# PatchPanel.net
KiCad netlist of a schematic drawn in EAGLE
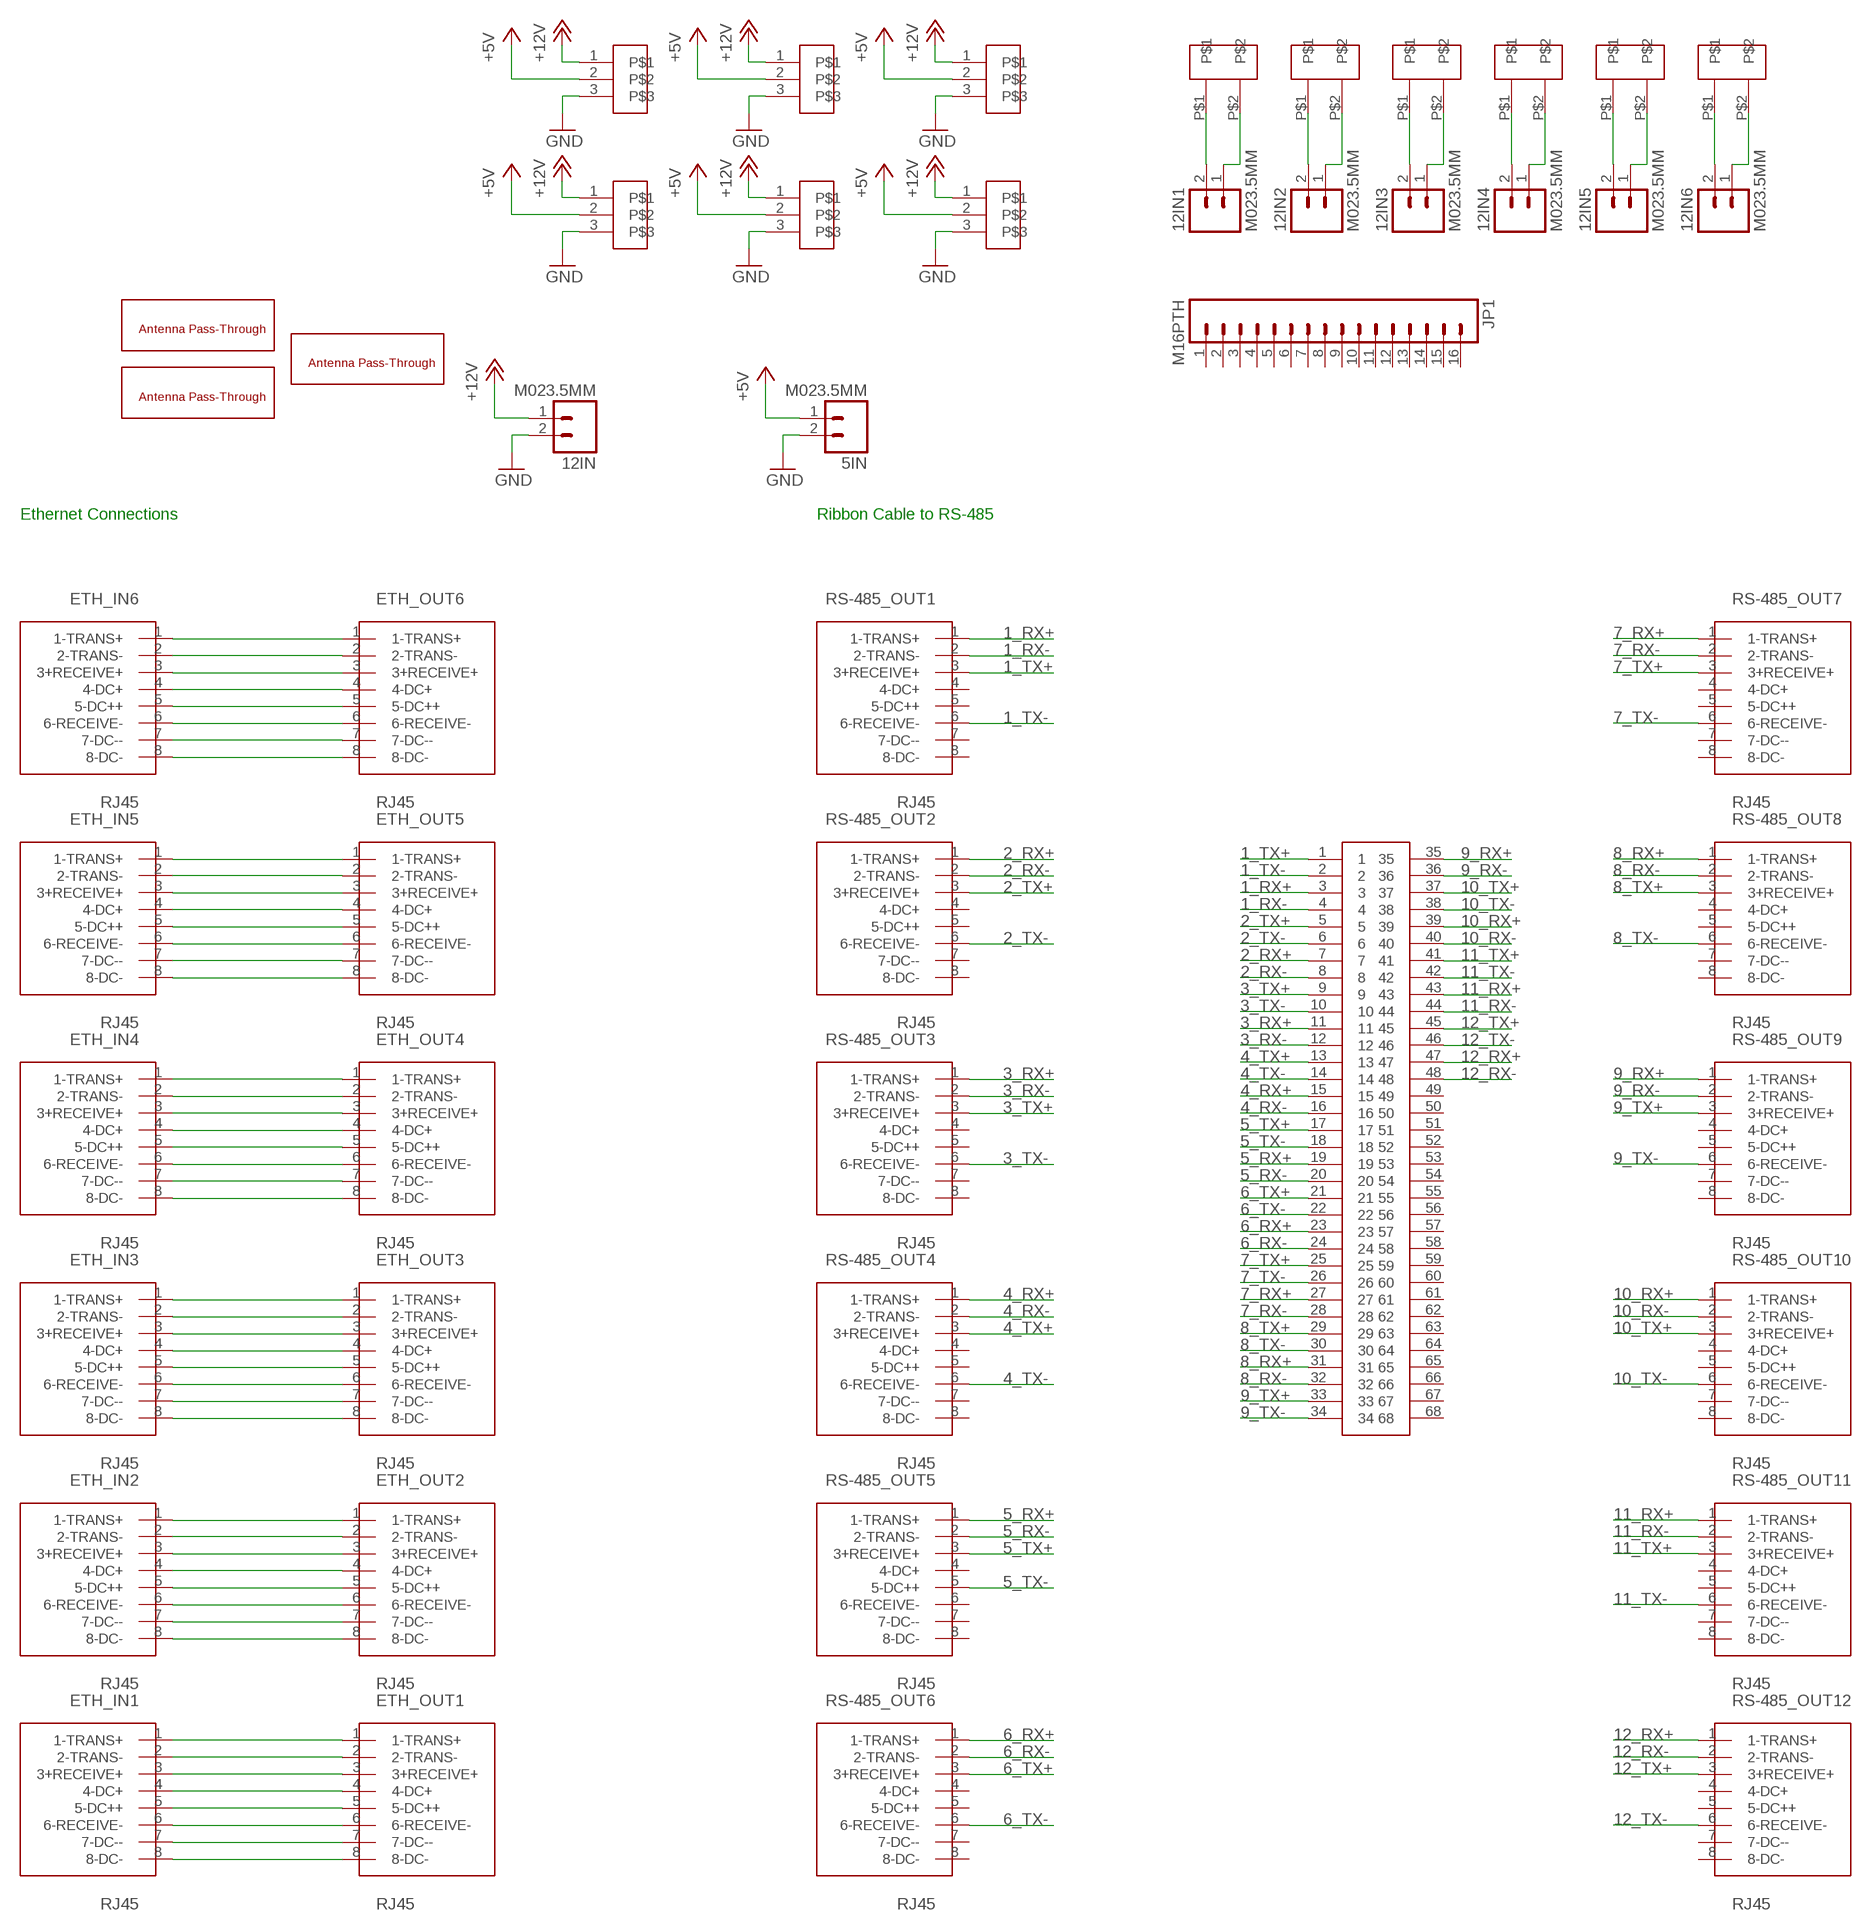
[diagram p0: schematic, sheet 1]

(export (version "E")
  (design (tool "Eeschema 10.0.6"))
  (components
    (comp (ref "5IN")
      (value "M023.5MM")
      (footprint "eagle-import:SCREWTERMINAL-3.5MM-2")
      (libsource (lib "eagle-import") (part "M023.5MM"))
    )
    (comp (ref "12IN")
      (value "M023.5MM")
      (footprint "eagle-import:SCREWTERMINAL-3.5MM-2")
      (libsource (lib "eagle-import") (part "M023.5MM"))
    )
    (comp (ref "12IN1")
      (value "M023.5MM")
      (footprint "eagle-import:SCREWTERMINAL-3.5MM-2")
      (libsource (lib "eagle-import") (part "M023.5MM"))
    )
    (comp (ref "12IN2")
      (value "M023.5MM")
      (footprint "eagle-import:SCREWTERMINAL-3.5MM-2")
      (libsource (lib "eagle-import") (part "M023.5MM"))
    )
    (comp (ref "12IN3")
      (value "M023.5MM")
      (footprint "eagle-import:SCREWTERMINAL-3.5MM-2")
      (libsource (lib "eagle-import") (part "M023.5MM"))
    )
    (comp (ref "12IN4")
      (value "M023.5MM")
      (footprint "eagle-import:SCREWTERMINAL-3.5MM-2")
      (libsource (lib "eagle-import") (part "M023.5MM"))
    )
    (comp (ref "12IN5")
      (value "M023.5MM")
      (footprint "eagle-import:SCREWTERMINAL-3.5MM-2")
      (libsource (lib "eagle-import") (part "M023.5MM"))
    )
    (comp (ref "12IN6")
      (value "M023.5MM")
      (footprint "eagle-import:SCREWTERMINAL-3.5MM-2")
      (libsource (lib "eagle-import") (part "M023.5MM"))
    )
    (comp (ref "ETH_IN1")
      (value "RJ45")
      (footprint "eagle-import:RJ45-CAT5E")
      (libsource (lib "eagle-import") (part "RJ45"))
    )
    (comp (ref "ETH_IN2")
      (value "RJ45")
      (footprint "eagle-import:RJ45-CAT5E")
      (libsource (lib "eagle-import") (part "RJ45"))
    )
    (comp (ref "ETH_IN3")
      (value "RJ45")
      (footprint "eagle-import:RJ45-CAT5E")
      (libsource (lib "eagle-import") (part "RJ45"))
    )
    (comp (ref "ETH_IN4")
      (value "RJ45")
      (footprint "eagle-import:RJ45-CAT5E")
      (libsource (lib "eagle-import") (part "RJ45"))
    )
    (comp (ref "ETH_IN5")
      (value "RJ45")
      (footprint "eagle-import:RJ45-CAT5E")
      (libsource (lib "eagle-import") (part "RJ45"))
    )
    (comp (ref "ETH_IN6")
      (value "RJ45")
      (footprint "eagle-import:RJ45-CAT5E")
      (libsource (lib "eagle-import") (part "RJ45"))
    )
    (comp (ref "ETH_OUT1")
      (value "RJ45")
      (footprint "eagle-import:RJ45-CAT5E")
      (libsource (lib "eagle-import") (part "RJ45"))
    )
    (comp (ref "ETH_OUT2")
      (value "RJ45")
      (footprint "eagle-import:RJ45-CAT5E")
      (libsource (lib "eagle-import") (part "RJ45"))
    )
    (comp (ref "ETH_OUT3")
      (value "RJ45")
      (footprint "eagle-import:RJ45-CAT5E")
      (libsource (lib "eagle-import") (part "RJ45"))
    )
    (comp (ref "ETH_OUT4")
      (value "RJ45")
      (footprint "eagle-import:RJ45-CAT5E")
      (libsource (lib "eagle-import") (part "RJ45"))
    )
    (comp (ref "ETH_OUT5")
      (value "RJ45")
      (footprint "eagle-import:RJ45-CAT5E")
      (libsource (lib "eagle-import") (part "RJ45"))
    )
    (comp (ref "ETH_OUT6")
      (value "RJ45")
      (footprint "eagle-import:RJ45-CAT5E")
      (libsource (lib "eagle-import") (part "RJ45"))
    )
    (comp (ref "JP1")
      (value "M16PTH")
      (footprint "eagle-import:1X16")
      (libsource (lib "eagle-import") (part "M16PTH"))
    )
    (comp (ref "RS-485_OUT1")
      (value "RJ45")
      (footprint "eagle-import:RJ45-CAT5E")
      (libsource (lib "eagle-import") (part "RJ45"))
    )
    (comp (ref "RS-485_OUT2")
      (value "RJ45")
      (footprint "eagle-import:RJ45-CAT5E")
      (libsource (lib "eagle-import") (part "RJ45"))
    )
    (comp (ref "RS-485_OUT3")
      (value "RJ45")
      (footprint "eagle-import:RJ45-CAT5E")
      (libsource (lib "eagle-import") (part "RJ45"))
    )
    (comp (ref "RS-485_OUT4")
      (value "RJ45")
      (footprint "eagle-import:RJ45-CAT5E")
      (libsource (lib "eagle-import") (part "RJ45"))
    )
    (comp (ref "RS-485_OUT5")
      (value "RJ45")
      (footprint "eagle-import:RJ45-CAT5E")
      (libsource (lib "eagle-import") (part "RJ45"))
    )
    (comp (ref "RS-485_OUT6")
      (value "RJ45")
      (footprint "eagle-import:RJ45-CAT5E")
      (libsource (lib "eagle-import") (part "RJ45"))
    )
    (comp (ref "RS-485_OUT7")
      (value "RJ45")
      (footprint "eagle-import:RJ45-CAT5E")
      (libsource (lib "eagle-import") (part "RJ45"))
    )
    (comp (ref "RS-485_OUT8")
      (value "RJ45")
      (footprint "eagle-import:RJ45-CAT5E")
      (libsource (lib "eagle-import") (part "RJ45"))
    )
    (comp (ref "RS-485_OUT9")
      (value "RJ45")
      (footprint "eagle-import:RJ45-CAT5E")
      (libsource (lib "eagle-import") (part "RJ45"))
    )
    (comp (ref "RS-485_OUT10")
      (value "RJ45")
      (footprint "eagle-import:RJ45-CAT5E")
      (libsource (lib "eagle-import") (part "RJ45"))
    )
    (comp (ref "RS-485_OUT11")
      (value "RJ45")
      (footprint "eagle-import:RJ45-CAT5E")
      (libsource (lib "eagle-import") (part "RJ45"))
    )
    (comp (ref "RS-485_OUT12")
      (value "RJ45")
      (footprint "eagle-import:RJ45-CAT5E")
      (libsource (lib "eagle-import") (part "RJ45"))
    )
    (comp (ref "U$1")
      (value "TB60050685100")
      (footprint "eagle-import:60050685100")
      (libsource (lib "eagle-import") (part "TB60050685100"))
    )
    (comp (ref "U$2")
      (value "3PIN")
      (footprint "eagle-import:0.93_")
      (libsource (lib "eagle-import") (part "3PIN"))
    )
    (comp (ref "U$3")
      (value "3PIN")
      (footprint "eagle-import:0.93_")
      (libsource (lib "eagle-import") (part "3PIN"))
    )
    (comp (ref "U$4")
      (value "3PIN")
      (footprint "eagle-import:0.93_")
      (libsource (lib "eagle-import") (part "3PIN"))
    )
    (comp (ref "U$5")
      (value "3PIN")
      (footprint "eagle-import:0.93_")
      (libsource (lib "eagle-import") (part "3PIN"))
    )
    (comp (ref "U$6")
      (value "3PIN")
      (footprint "eagle-import:0.93_")
      (libsource (lib "eagle-import") (part "3PIN"))
    )
    (comp (ref "U$7")
      (value "3PIN")
      (footprint "eagle-import:0.93_")
      (libsource (lib "eagle-import") (part "3PIN"))
    )
    (comp (ref "U$8")
      (value "MLX-2")
      (footprint "eagle-import:42002-2")
      (libsource (lib "eagle-import") (part "MLX-2"))
    )
    (comp (ref "U$9")
      (value "MLX-2")
      (footprint "eagle-import:42002-2")
      (libsource (lib "eagle-import") (part "MLX-2"))
    )
    (comp (ref "U$10")
      (value "MLX-2")
      (footprint "eagle-import:42002-2")
      (libsource (lib "eagle-import") (part "MLX-2"))
    )
    (comp (ref "U$11")
      (value "MLX-2")
      (footprint "eagle-import:42002-2")
      (libsource (lib "eagle-import") (part "MLX-2"))
    )
    (comp (ref "U$12")
      (value "MLX-2")
      (footprint "eagle-import:42002-2")
      (libsource (lib "eagle-import") (part "MLX-2"))
    )
    (comp (ref "U$13")
      (value "MLX-2")
      (footprint "eagle-import:42002-2")
      (libsource (lib "eagle-import") (part "MLX-2"))
    )
    (comp (ref "U$14")
      (value "N-TYPE-THRU")
      (footprint "eagle-import:N-TYPE")
      (libsource (lib "eagle-import") (part "N-TYPE-THRU"))
    )
    (comp (ref "U$15")
      (value "N-TYPE-THRU")
      (footprint "eagle-import:N-TYPE")
      (libsource (lib "eagle-import") (part "N-TYPE-THRU"))
    )
    (comp (ref "U$16")
      (value "SMA-THRU")
      (footprint "eagle-import:SMA")
      (libsource (lib "eagle-import") (part "SMA-THRU"))
    )
  )
  (nets
    (net (code "1") (name "+5V") (class "Default")
      (node (ref "5IN") (pin "1") (pinfunction "1_1") (pintype "passive"))
      (node (ref "U$2") (pin "2") (pinfunction "P$2_2") (pintype "bidirectional"))
      (node (ref "U$3") (pin "2") (pinfunction "P$2_2") (pintype "bidirectional"))
      (node (ref "U$4") (pin "2") (pinfunction "P$2_2") (pintype "bidirectional"))
      (node (ref "U$5") (pin "2") (pinfunction "P$2_2") (pintype "bidirectional"))
      (node (ref "U$6") (pin "2") (pinfunction "P$2_2") (pintype "bidirectional"))
      (node (ref "U$7") (pin "2") (pinfunction "P$2_2") (pintype "bidirectional"))
    )
    (net (code "2") (name "+12V") (class "Default")
      (node (ref "12IN") (pin "1") (pinfunction "1_1") (pintype "passive"))
      (node (ref "U$2") (pin "1") (pinfunction "P$1_1") (pintype "bidirectional"))
      (node (ref "U$3") (pin "1") (pinfunction "P$1_1") (pintype "bidirectional"))
      (node (ref "U$4") (pin "1") (pinfunction "P$1_1") (pintype "bidirectional"))
      (node (ref "U$5") (pin "1") (pinfunction "P$1_1") (pintype "bidirectional"))
      (node (ref "U$6") (pin "1") (pinfunction "P$1_1") (pintype "bidirectional"))
      (node (ref "U$7") (pin "1") (pinfunction "P$1_1") (pintype "bidirectional"))
    )
    (net (code "3") (name "/1_RX+") (class "Default")
      (node (ref "RS-485_OUT1") (pin "1") (pinfunction "1-TRANS+_1") (pintype "bidirectional"))
      (node (ref "U$1") (pin "3") (pinfunction "3_3") (pintype "bidirectional"))
    )
    (net (code "4") (name "/1_RX-") (class "Default")
      (node (ref "RS-485_OUT1") (pin "2") (pinfunction "2-TRANS-_2") (pintype "bidirectional"))
      (node (ref "U$1") (pin "4") (pinfunction "4_4") (pintype "bidirectional"))
    )
    (net (code "5") (name "/1_TX+") (class "Default")
      (node (ref "RS-485_OUT1") (pin "3") (pinfunction "3+RECEIVE+_3") (pintype "bidirectional"))
      (node (ref "U$1") (pin "1") (pinfunction "1_1") (pintype "bidirectional"))
    )
    (net (code "6") (name "/1_TX-") (class "Default")
      (node (ref "RS-485_OUT1") (pin "6") (pinfunction "6-RECEIVE-_6") (pintype "bidirectional"))
      (node (ref "U$1") (pin "2") (pinfunction "2_2") (pintype "bidirectional"))
    )
    (net (code "7") (name "/2_RX+") (class "Default")
      (node (ref "RS-485_OUT2") (pin "1") (pinfunction "1-TRANS+_1") (pintype "bidirectional"))
      (node (ref "U$1") (pin "7") (pinfunction "7_7") (pintype "bidirectional"))
    )
    (net (code "8") (name "/2_RX-") (class "Default")
      (node (ref "RS-485_OUT2") (pin "2") (pinfunction "2-TRANS-_2") (pintype "bidirectional"))
      (node (ref "U$1") (pin "8") (pinfunction "8_8") (pintype "bidirectional"))
    )
    (net (code "9") (name "/2_TX+") (class "Default")
      (node (ref "RS-485_OUT2") (pin "3") (pinfunction "3+RECEIVE+_3") (pintype "bidirectional"))
      (node (ref "U$1") (pin "5") (pinfunction "5_5") (pintype "bidirectional"))
    )
    (net (code "10") (name "/2_TX-") (class "Default")
      (node (ref "RS-485_OUT2") (pin "6") (pinfunction "6-RECEIVE-_6") (pintype "bidirectional"))
      (node (ref "U$1") (pin "6") (pinfunction "6_6") (pintype "bidirectional"))
    )
    (net (code "11") (name "/3_RX+") (class "Default")
      (node (ref "RS-485_OUT3") (pin "1") (pinfunction "1-TRANS+_1") (pintype "bidirectional"))
      (node (ref "U$1") (pin "11") (pinfunction "11_11") (pintype "bidirectional"))
    )
    (net (code "12") (name "/3_RX-") (class "Default")
      (node (ref "RS-485_OUT3") (pin "2") (pinfunction "2-TRANS-_2") (pintype "bidirectional"))
      (node (ref "U$1") (pin "12") (pinfunction "12_12") (pintype "bidirectional"))
    )
    (net (code "13") (name "/3_TX+") (class "Default")
      (node (ref "RS-485_OUT3") (pin "3") (pinfunction "3+RECEIVE+_3") (pintype "bidirectional"))
      (node (ref "U$1") (pin "9") (pinfunction "9_9") (pintype "bidirectional"))
    )
    (net (code "14") (name "/3_TX-") (class "Default")
      (node (ref "RS-485_OUT3") (pin "6") (pinfunction "6-RECEIVE-_6") (pintype "bidirectional"))
      (node (ref "U$1") (pin "10") (pinfunction "10_10") (pintype "bidirectional"))
    )
    (net (code "15") (name "/4_RX+") (class "Default")
      (node (ref "RS-485_OUT4") (pin "1") (pinfunction "1-TRANS+_1") (pintype "bidirectional"))
      (node (ref "U$1") (pin "15") (pinfunction "15_15") (pintype "bidirectional"))
    )
    (net (code "16") (name "/4_RX-") (class "Default")
      (node (ref "RS-485_OUT4") (pin "2") (pinfunction "2-TRANS-_2") (pintype "bidirectional"))
      (node (ref "U$1") (pin "16") (pinfunction "16_16") (pintype "bidirectional"))
    )
    (net (code "17") (name "/4_TX+") (class "Default")
      (node (ref "RS-485_OUT4") (pin "3") (pinfunction "3+RECEIVE+_3") (pintype "bidirectional"))
      (node (ref "U$1") (pin "13") (pinfunction "13_13") (pintype "bidirectional"))
    )
    (net (code "18") (name "/4_TX-") (class "Default")
      (node (ref "RS-485_OUT4") (pin "6") (pinfunction "6-RECEIVE-_6") (pintype "bidirectional"))
      (node (ref "U$1") (pin "14") (pinfunction "14_14") (pintype "bidirectional"))
    )
    (net (code "19") (name "/5_RX+") (class "Default")
      (node (ref "RS-485_OUT5") (pin "1") (pinfunction "1-TRANS+_1") (pintype "bidirectional"))
      (node (ref "U$1") (pin "19") (pinfunction "19_19") (pintype "bidirectional"))
    )
    (net (code "20") (name "/5_RX-") (class "Default")
      (node (ref "RS-485_OUT5") (pin "2") (pinfunction "2-TRANS-_2") (pintype "bidirectional"))
      (node (ref "U$1") (pin "20") (pinfunction "20_20") (pintype "bidirectional"))
    )
    (net (code "21") (name "/5_TX+") (class "Default")
      (node (ref "RS-485_OUT5") (pin "3") (pinfunction "3+RECEIVE+_3") (pintype "bidirectional"))
      (node (ref "U$1") (pin "17") (pinfunction "17_17") (pintype "bidirectional"))
    )
    (net (code "22") (name "/5_TX-") (class "Default")
      (node (ref "RS-485_OUT5") (pin "5") (pinfunction "5-DC++_5") (pintype "bidirectional"))
      (node (ref "U$1") (pin "18") (pinfunction "18_18") (pintype "bidirectional"))
    )
    (net (code "23") (name "/6_RX+") (class "Default")
      (node (ref "RS-485_OUT6") (pin "1") (pinfunction "1-TRANS+_1") (pintype "bidirectional"))
      (node (ref "U$1") (pin "23") (pinfunction "23_23") (pintype "bidirectional"))
    )
    (net (code "24") (name "/6_RX-") (class "Default")
      (node (ref "RS-485_OUT6") (pin "2") (pinfunction "2-TRANS-_2") (pintype "bidirectional"))
      (node (ref "U$1") (pin "24") (pinfunction "24_24") (pintype "bidirectional"))
    )
    (net (code "25") (name "/6_TX+") (class "Default")
      (node (ref "RS-485_OUT6") (pin "3") (pinfunction "3+RECEIVE+_3") (pintype "bidirectional"))
      (node (ref "U$1") (pin "21") (pinfunction "21_21") (pintype "bidirectional"))
    )
    (net (code "26") (name "/6_TX-") (class "Default")
      (node (ref "RS-485_OUT6") (pin "6") (pinfunction "6-RECEIVE-_6") (pintype "bidirectional"))
      (node (ref "U$1") (pin "22") (pinfunction "22_22") (pintype "bidirectional"))
    )
    (net (code "27") (name "/7_RX+") (class "Default")
      (node (ref "RS-485_OUT7") (pin "1") (pinfunction "1-TRANS+_1") (pintype "bidirectional"))
      (node (ref "U$1") (pin "27") (pinfunction "27_27") (pintype "bidirectional"))
    )
    (net (code "28") (name "/7_RX-") (class "Default")
      (node (ref "RS-485_OUT7") (pin "2") (pinfunction "2-TRANS-_2") (pintype "bidirectional"))
      (node (ref "U$1") (pin "28") (pinfunction "28_28") (pintype "bidirectional"))
    )
    (net (code "29") (name "/7_TX+") (class "Default")
      (node (ref "RS-485_OUT7") (pin "3") (pinfunction "3+RECEIVE+_3") (pintype "bidirectional"))
      (node (ref "U$1") (pin "25") (pinfunction "25_25") (pintype "bidirectional"))
    )
    (net (code "30") (name "/7_TX-") (class "Default")
      (node (ref "RS-485_OUT7") (pin "6") (pinfunction "6-RECEIVE-_6") (pintype "bidirectional"))
      (node (ref "U$1") (pin "26") (pinfunction "26_26") (pintype "bidirectional"))
    )
    (net (code "31") (name "/8_RX+") (class "Default")
      (node (ref "RS-485_OUT8") (pin "1") (pinfunction "1-TRANS+_1") (pintype "bidirectional"))
      (node (ref "U$1") (pin "31") (pinfunction "31_31") (pintype "bidirectional"))
    )
    (net (code "32") (name "/8_RX-") (class "Default")
      (node (ref "RS-485_OUT8") (pin "2") (pinfunction "2-TRANS-_2") (pintype "bidirectional"))
      (node (ref "U$1") (pin "32") (pinfunction "32_32") (pintype "bidirectional"))
    )
    (net (code "33") (name "/8_TX+") (class "Default")
      (node (ref "RS-485_OUT8") (pin "3") (pinfunction "3+RECEIVE+_3") (pintype "bidirectional"))
      (node (ref "U$1") (pin "29") (pinfunction "29_29") (pintype "bidirectional"))
    )
    (net (code "34") (name "/8_TX-") (class "Default")
      (node (ref "RS-485_OUT8") (pin "6") (pinfunction "6-RECEIVE-_6") (pintype "bidirectional"))
      (node (ref "U$1") (pin "30") (pinfunction "30_30") (pintype "bidirectional"))
    )
    (net (code "35") (name "/9_RX+") (class "Default")
      (node (ref "RS-485_OUT9") (pin "1") (pinfunction "1-TRANS+_1") (pintype "bidirectional"))
      (node (ref "U$1") (pin "35") (pinfunction "35_35") (pintype "bidirectional"))
    )
    (net (code "36") (name "/9_RX-") (class "Default")
      (node (ref "RS-485_OUT9") (pin "2") (pinfunction "2-TRANS-_2") (pintype "bidirectional"))
      (node (ref "U$1") (pin "36") (pinfunction "36_36") (pintype "bidirectional"))
    )
    (net (code "37") (name "/9_TX+") (class "Default")
      (node (ref "RS-485_OUT9") (pin "3") (pinfunction "3+RECEIVE+_3") (pintype "bidirectional"))
      (node (ref "U$1") (pin "33") (pinfunction "33_33") (pintype "bidirectional"))
    )
    (net (code "38") (name "/9_TX-") (class "Default")
      (node (ref "RS-485_OUT9") (pin "6") (pinfunction "6-RECEIVE-_6") (pintype "bidirectional"))
      (node (ref "U$1") (pin "34") (pinfunction "34_34") (pintype "bidirectional"))
    )
    (net (code "39") (name "/10_RX+") (class "Default")
      (node (ref "RS-485_OUT10") (pin "1") (pinfunction "1-TRANS+_1") (pintype "bidirectional"))
      (node (ref "U$1") (pin "39") (pinfunction "39_39") (pintype "bidirectional"))
    )
    (net (code "40") (name "/10_RX-") (class "Default")
      (node (ref "RS-485_OUT10") (pin "2") (pinfunction "2-TRANS-_2") (pintype "bidirectional"))
      (node (ref "U$1") (pin "40") (pinfunction "40_40") (pintype "bidirectional"))
    )
    (net (code "41") (name "/10_TX+") (class "Default")
      (node (ref "RS-485_OUT10") (pin "3") (pinfunction "3+RECEIVE+_3") (pintype "bidirectional"))
      (node (ref "U$1") (pin "37") (pinfunction "37_37") (pintype "bidirectional"))
    )
    (net (code "42") (name "/10_TX-") (class "Default")
      (node (ref "RS-485_OUT10") (pin "6") (pinfunction "6-RECEIVE-_6") (pintype "bidirectional"))
      (node (ref "U$1") (pin "38") (pinfunction "38_38") (pintype "bidirectional"))
    )
    (net (code "43") (name "/11_RX+") (class "Default")
      (node (ref "RS-485_OUT11") (pin "1") (pinfunction "1-TRANS+_1") (pintype "bidirectional"))
      (node (ref "U$1") (pin "43") (pinfunction "43_43") (pintype "bidirectional"))
    )
    (net (code "44") (name "/11_RX-") (class "Default")
      (node (ref "RS-485_OUT11") (pin "2") (pinfunction "2-TRANS-_2") (pintype "bidirectional"))
      (node (ref "U$1") (pin "44") (pinfunction "44_44") (pintype "bidirectional"))
    )
    (net (code "45") (name "/11_TX+") (class "Default")
      (node (ref "RS-485_OUT11") (pin "3") (pinfunction "3+RECEIVE+_3") (pintype "bidirectional"))
      (node (ref "U$1") (pin "41") (pinfunction "41_41") (pintype "bidirectional"))
    )
    (net (code "46") (name "/11_TX-") (class "Default")
      (node (ref "RS-485_OUT11") (pin "6") (pinfunction "6-RECEIVE-_6") (pintype "bidirectional"))
      (node (ref "U$1") (pin "42") (pinfunction "42_42") (pintype "bidirectional"))
    )
    (net (code "47") (name "/12_RX+") (class "Default")
      (node (ref "RS-485_OUT12") (pin "1") (pinfunction "1-TRANS+_1") (pintype "bidirectional"))
      (node (ref "U$1") (pin "47") (pinfunction "47_47") (pintype "bidirectional"))
    )
    (net (code "48") (name "/12_RX-") (class "Default")
      (node (ref "RS-485_OUT12") (pin "2") (pinfunction "2-TRANS-_2") (pintype "bidirectional"))
      (node (ref "U$1") (pin "48") (pinfunction "48_48") (pintype "bidirectional"))
    )
    (net (code "49") (name "/12_TX+") (class "Default")
      (node (ref "RS-485_OUT12") (pin "3") (pinfunction "3+RECEIVE+_3") (pintype "bidirectional"))
      (node (ref "U$1") (pin "45") (pinfunction "45_45") (pintype "bidirectional"))
    )
    (net (code "50") (name "/12_TX-") (class "Default")
      (node (ref "RS-485_OUT12") (pin "6") (pinfunction "6-RECEIVE-_6") (pintype "bidirectional"))
      (node (ref "U$1") (pin "46") (pinfunction "46_46") (pintype "bidirectional"))
    )
    (net (code "51") (name "GND") (class "Default")
      (node (ref "12IN") (pin "2") (pinfunction "2_2") (pintype "passive"))
      (node (ref "5IN") (pin "2") (pinfunction "2_2") (pintype "passive"))
      (node (ref "U$2") (pin "3") (pinfunction "P$3_3") (pintype "bidirectional"))
      (node (ref "U$3") (pin "3") (pinfunction "P$3_3") (pintype "bidirectional"))
      (node (ref "U$4") (pin "3") (pinfunction "P$3_3") (pintype "bidirectional"))
      (node (ref "U$5") (pin "3") (pinfunction "P$3_3") (pintype "bidirectional"))
      (node (ref "U$6") (pin "3") (pinfunction "P$3_3") (pintype "bidirectional"))
      (node (ref "U$7") (pin "3") (pinfunction "P$3_3") (pintype "bidirectional"))
    )
    (net (code "52") (name "Net-(12IN1-Pad1)") (class "Default")
      (node (ref "12IN1") (pin "1") (pinfunction "1_1") (pintype "passive"))
      (node (ref "U$8") (pin "P$2") (pinfunction "P$2_P$2") (pintype "bidirectional"))
    )
    (net (code "53") (name "Net-(12IN1-Pad2)") (class "Default")
      (node (ref "12IN1") (pin "2") (pinfunction "2_2") (pintype "passive"))
      (node (ref "U$8") (pin "P$1") (pinfunction "P$1_P$1") (pintype "bidirectional"))
    )
    (net (code "54") (name "Net-(12IN2-Pad1)") (class "Default")
      (node (ref "12IN2") (pin "1") (pinfunction "1_1") (pintype "passive"))
      (node (ref "U$9") (pin "P$2") (pinfunction "P$2_P$2") (pintype "bidirectional"))
    )
    (net (code "55") (name "Net-(12IN2-Pad2)") (class "Default")
      (node (ref "12IN2") (pin "2") (pinfunction "2_2") (pintype "passive"))
      (node (ref "U$9") (pin "P$1") (pinfunction "P$1_P$1") (pintype "bidirectional"))
    )
    (net (code "56") (name "Net-(12IN3-Pad1)") (class "Default")
      (node (ref "12IN3") (pin "1") (pinfunction "1_1") (pintype "passive"))
      (node (ref "U$10") (pin "P$2") (pinfunction "P$2_P$2") (pintype "bidirectional"))
    )
    (net (code "57") (name "Net-(12IN3-Pad2)") (class "Default")
      (node (ref "12IN3") (pin "2") (pinfunction "2_2") (pintype "passive"))
      (node (ref "U$10") (pin "P$1") (pinfunction "P$1_P$1") (pintype "bidirectional"))
    )
    (net (code "58") (name "Net-(12IN4-Pad1)") (class "Default")
      (node (ref "12IN4") (pin "1") (pinfunction "1_1") (pintype "passive"))
      (node (ref "U$11") (pin "P$2") (pinfunction "P$2_P$2") (pintype "bidirectional"))
    )
    (net (code "59") (name "Net-(12IN4-Pad2)") (class "Default")
      (node (ref "12IN4") (pin "2") (pinfunction "2_2") (pintype "passive"))
      (node (ref "U$11") (pin "P$1") (pinfunction "P$1_P$1") (pintype "bidirectional"))
    )
    (net (code "60") (name "Net-(12IN5-Pad1)") (class "Default")
      (node (ref "12IN5") (pin "1") (pinfunction "1_1") (pintype "passive"))
      (node (ref "U$12") (pin "P$2") (pinfunction "P$2_P$2") (pintype "bidirectional"))
    )
    (net (code "61") (name "Net-(12IN5-Pad2)") (class "Default")
      (node (ref "12IN5") (pin "2") (pinfunction "2_2") (pintype "passive"))
      (node (ref "U$12") (pin "P$1") (pinfunction "P$1_P$1") (pintype "bidirectional"))
    )
    (net (code "62") (name "Net-(12IN6-Pad1)") (class "Default")
      (node (ref "12IN6") (pin "1") (pinfunction "1_1") (pintype "passive"))
      (node (ref "U$13") (pin "P$2") (pinfunction "P$2_P$2") (pintype "bidirectional"))
    )
    (net (code "63") (name "Net-(12IN6-Pad2)") (class "Default")
      (node (ref "12IN6") (pin "2") (pinfunction "2_2") (pintype "passive"))
      (node (ref "U$13") (pin "P$1") (pinfunction "P$1_P$1") (pintype "bidirectional"))
    )
    (net (code "64") (name "Net-(ETH_IN1-1-TRANS+)") (class "Default")
      (node (ref "ETH_IN1") (pin "1") (pinfunction "1-TRANS+_1") (pintype "bidirectional"))
      (node (ref "ETH_OUT1") (pin "1") (pinfunction "1-TRANS+_1") (pintype "bidirectional"))
    )
    (net (code "65") (name "Net-(ETH_IN1-2-TRANS-)") (class "Default")
      (node (ref "ETH_IN1") (pin "2") (pinfunction "2-TRANS-_2") (pintype "bidirectional"))
      (node (ref "ETH_OUT1") (pin "2") (pinfunction "2-TRANS-_2") (pintype "bidirectional"))
    )
    (net (code "66") (name "Net-(ETH_IN1-3+RECEIVE+)") (class "Default")
      (node (ref "ETH_IN1") (pin "3") (pinfunction "3+RECEIVE+_3") (pintype "bidirectional"))
      (node (ref "ETH_OUT1") (pin "3") (pinfunction "3+RECEIVE+_3") (pintype "bidirectional"))
    )
    (net (code "67") (name "Net-(ETH_IN1-4-DC+)") (class "Default")
      (node (ref "ETH_IN1") (pin "4") (pinfunction "4-DC+_4") (pintype "bidirectional"))
      (node (ref "ETH_OUT1") (pin "4") (pinfunction "4-DC+_4") (pintype "bidirectional"))
    )
    (net (code "68") (name "Net-(ETH_IN1-5-DC++)") (class "Default")
      (node (ref "ETH_IN1") (pin "5") (pinfunction "5-DC++_5") (pintype "bidirectional"))
      (node (ref "ETH_OUT1") (pin "5") (pinfunction "5-DC++_5") (pintype "bidirectional"))
    )
    (net (code "69") (name "Net-(ETH_IN1-6-RECEIVE-)") (class "Default")
      (node (ref "ETH_IN1") (pin "6") (pinfunction "6-RECEIVE-_6") (pintype "bidirectional"))
      (node (ref "ETH_OUT1") (pin "6") (pinfunction "6-RECEIVE-_6") (pintype "bidirectional"))
    )
    (net (code "70") (name "Net-(ETH_IN1-7-DC--)") (class "Default")
      (node (ref "ETH_IN1") (pin "7") (pinfunction "7-DC--_7") (pintype "bidirectional"))
      (node (ref "ETH_OUT1") (pin "7") (pinfunction "7-DC--_7") (pintype "bidirectional"))
    )
    (net (code "71") (name "Net-(ETH_IN1-8-DC-)") (class "Default")
      (node (ref "ETH_IN1") (pin "8") (pinfunction "8-DC-_8") (pintype "bidirectional"))
      (node (ref "ETH_OUT1") (pin "8") (pinfunction "8-DC-_8") (pintype "bidirectional"))
    )
    (net (code "72") (name "Net-(ETH_IN2-1-TRANS+)") (class "Default")
      (node (ref "ETH_IN2") (pin "1") (pinfunction "1-TRANS+_1") (pintype "bidirectional"))
      (node (ref "ETH_OUT2") (pin "1") (pinfunction "1-TRANS+_1") (pintype "bidirectional"))
    )
    (net (code "73") (name "Net-(ETH_IN2-2-TRANS-)") (class "Default")
      (node (ref "ETH_IN2") (pin "2") (pinfunction "2-TRANS-_2") (pintype "bidirectional"))
      (node (ref "ETH_OUT2") (pin "2") (pinfunction "2-TRANS-_2") (pintype "bidirectional"))
    )
    (net (code "74") (name "Net-(ETH_IN2-3+RECEIVE+)") (class "Default")
      (node (ref "ETH_IN2") (pin "3") (pinfunction "3+RECEIVE+_3") (pintype "bidirectional"))
      (node (ref "ETH_OUT2") (pin "3") (pinfunction "3+RECEIVE+_3") (pintype "bidirectional"))
    )
    (net (code "75") (name "Net-(ETH_IN2-4-DC+)") (class "Default")
      (node (ref "ETH_IN2") (pin "4") (pinfunction "4-DC+_4") (pintype "bidirectional"))
      (node (ref "ETH_OUT2") (pin "4") (pinfunction "4-DC+_4") (pintype "bidirectional"))
    )
    (net (code "76") (name "Net-(ETH_IN2-5-DC++)") (class "Default")
      (node (ref "ETH_IN2") (pin "5") (pinfunction "5-DC++_5") (pintype "bidirectional"))
      (node (ref "ETH_OUT2") (pin "5") (pinfunction "5-DC++_5") (pintype "bidirectional"))
    )
    (net (code "77") (name "Net-(ETH_IN2-6-RECEIVE-)") (class "Default")
      (node (ref "ETH_IN2") (pin "6") (pinfunction "6-RECEIVE-_6") (pintype "bidirectional"))
      (node (ref "ETH_OUT2") (pin "6") (pinfunction "6-RECEIVE-_6") (pintype "bidirectional"))
    )
    (net (code "78") (name "Net-(ETH_IN2-7-DC--)") (class "Default")
      (node (ref "ETH_IN2") (pin "7") (pinfunction "7-DC--_7") (pintype "bidirectional"))
      (node (ref "ETH_OUT2") (pin "7") (pinfunction "7-DC--_7") (pintype "bidirectional"))
    )
    (net (code "79") (name "Net-(ETH_IN2-8-DC-)") (class "Default")
      (node (ref "ETH_IN2") (pin "8") (pinfunction "8-DC-_8") (pintype "bidirectional"))
      (node (ref "ETH_OUT2") (pin "8") (pinfunction "8-DC-_8") (pintype "bidirectional"))
    )
    (net (code "80") (name "Net-(ETH_IN3-1-TRANS+)") (class "Default")
      (node (ref "ETH_IN3") (pin "1") (pinfunction "1-TRANS+_1") (pintype "bidirectional"))
      (node (ref "ETH_OUT3") (pin "1") (pinfunction "1-TRANS+_1") (pintype "bidirectional"))
    )
    (net (code "81") (name "Net-(ETH_IN3-2-TRANS-)") (class "Default")
      (node (ref "ETH_IN3") (pin "2") (pinfunction "2-TRANS-_2") (pintype "bidirectional"))
      (node (ref "ETH_OUT3") (pin "2") (pinfunction "2-TRANS-_2") (pintype "bidirectional"))
    )
    (net (code "82") (name "Net-(ETH_IN3-3+RECEIVE+)") (class "Default")
      (node (ref "ETH_IN3") (pin "3") (pinfunction "3+RECEIVE+_3") (pintype "bidirectional"))
      (node (ref "ETH_OUT3") (pin "3") (pinfunction "3+RECEIVE+_3") (pintype "bidirectional"))
    )
    (net (code "83") (name "Net-(ETH_IN3-4-DC+)") (class "Default")
      (node (ref "ETH_IN3") (pin "4") (pinfunction "4-DC+_4") (pintype "bidirectional"))
      (node (ref "ETH_OUT3") (pin "4") (pinfunction "4-DC+_4") (pintype "bidirectional"))
    )
    (net (code "84") (name "Net-(ETH_IN3-5-DC++)") (class "Default")
      (node (ref "ETH_IN3") (pin "5") (pinfunction "5-DC++_5") (pintype "bidirectional"))
      (node (ref "ETH_OUT3") (pin "5") (pinfunction "5-DC++_5") (pintype "bidirectional"))
    )
    (net (code "85") (name "Net-(ETH_IN3-6-RECEIVE-)") (class "Default")
      (node (ref "ETH_IN3") (pin "6") (pinfunction "6-RECEIVE-_6") (pintype "bidirectional"))
      (node (ref "ETH_OUT3") (pin "6") (pinfunction "6-RECEIVE-_6") (pintype "bidirectional"))
    )
    (net (code "86") (name "Net-(ETH_IN3-7-DC--)") (class "Default")
      (node (ref "ETH_IN3") (pin "7") (pinfunction "7-DC--_7") (pintype "bidirectional"))
      (node (ref "ETH_OUT3") (pin "7") (pinfunction "7-DC--_7") (pintype "bidirectional"))
    )
    (net (code "87") (name "Net-(ETH_IN3-8-DC-)") (class "Default")
      (node (ref "ETH_IN3") (pin "8") (pinfunction "8-DC-_8") (pintype "bidirectional"))
      (node (ref "ETH_OUT3") (pin "8") (pinfunction "8-DC-_8") (pintype "bidirectional"))
    )
    (net (code "88") (name "Net-(ETH_IN4-1-TRANS+)") (class "Default")
      (node (ref "ETH_IN4") (pin "1") (pinfunction "1-TRANS+_1") (pintype "bidirectional"))
      (node (ref "ETH_OUT4") (pin "1") (pinfunction "1-TRANS+_1") (pintype "bidirectional"))
    )
    (net (code "89") (name "Net-(ETH_IN4-2-TRANS-)") (class "Default")
      (node (ref "ETH_IN4") (pin "2") (pinfunction "2-TRANS-_2") (pintype "bidirectional"))
      (node (ref "ETH_OUT4") (pin "2") (pinfunction "2-TRANS-_2") (pintype "bidirectional"))
    )
    (net (code "90") (name "Net-(ETH_IN4-3+RECEIVE+)") (class "Default")
      (node (ref "ETH_IN4") (pin "3") (pinfunction "3+RECEIVE+_3") (pintype "bidirectional"))
      (node (ref "ETH_OUT4") (pin "3") (pinfunction "3+RECEIVE+_3") (pintype "bidirectional"))
    )
    (net (code "91") (name "Net-(ETH_IN4-4-DC+)") (class "Default")
      (node (ref "ETH_IN4") (pin "4") (pinfunction "4-DC+_4") (pintype "bidirectional"))
      (node (ref "ETH_OUT4") (pin "4") (pinfunction "4-DC+_4") (pintype "bidirectional"))
    )
    (net (code "92") (name "Net-(ETH_IN4-5-DC++)") (class "Default")
      (node (ref "ETH_IN4") (pin "5") (pinfunction "5-DC++_5") (pintype "bidirectional"))
      (node (ref "ETH_OUT4") (pin "5") (pinfunction "5-DC++_5") (pintype "bidirectional"))
    )
    (net (code "93") (name "Net-(ETH_IN4-6-RECEIVE-)") (class "Default")
      (node (ref "ETH_IN4") (pin "6") (pinfunction "6-RECEIVE-_6") (pintype "bidirectional"))
      (node (ref "ETH_OUT4") (pin "6") (pinfunction "6-RECEIVE-_6") (pintype "bidirectional"))
    )
    (net (code "94") (name "Net-(ETH_IN4-7-DC--)") (class "Default")
      (node (ref "ETH_IN4") (pin "7") (pinfunction "7-DC--_7") (pintype "bidirectional"))
      (node (ref "ETH_OUT4") (pin "7") (pinfunction "7-DC--_7") (pintype "bidirectional"))
    )
    (net (code "95") (name "Net-(ETH_IN4-8-DC-)") (class "Default")
      (node (ref "ETH_IN4") (pin "8") (pinfunction "8-DC-_8") (pintype "bidirectional"))
      (node (ref "ETH_OUT4") (pin "8") (pinfunction "8-DC-_8") (pintype "bidirectional"))
    )
    (net (code "96") (name "Net-(ETH_IN5-1-TRANS+)") (class "Default")
      (node (ref "ETH_IN5") (pin "1") (pinfunction "1-TRANS+_1") (pintype "bidirectional"))
      (node (ref "ETH_OUT5") (pin "1") (pinfunction "1-TRANS+_1") (pintype "bidirectional"))
    )
    (net (code "97") (name "Net-(ETH_IN5-2-TRANS-)") (class "Default")
      (node (ref "ETH_IN5") (pin "2") (pinfunction "2-TRANS-_2") (pintype "bidirectional"))
      (node (ref "ETH_OUT5") (pin "2") (pinfunction "2-TRANS-_2") (pintype "bidirectional"))
    )
    (net (code "98") (name "Net-(ETH_IN5-3+RECEIVE+)") (class "Default")
      (node (ref "ETH_IN5") (pin "3") (pinfunction "3+RECEIVE+_3") (pintype "bidirectional"))
      (node (ref "ETH_OUT5") (pin "3") (pinfunction "3+RECEIVE+_3") (pintype "bidirectional"))
    )
    (net (code "99") (name "Net-(ETH_IN5-4-DC+)") (class "Default")
      (node (ref "ETH_IN5") (pin "4") (pinfunction "4-DC+_4") (pintype "bidirectional"))
      (node (ref "ETH_OUT5") (pin "4") (pinfunction "4-DC+_4") (pintype "bidirectional"))
    )
    (net (code "100") (name "Net-(ETH_IN5-5-DC++)") (class "Default")
      (node (ref "ETH_IN5") (pin "5") (pinfunction "5-DC++_5") (pintype "bidirectional"))
      (node (ref "ETH_OUT5") (pin "5") (pinfunction "5-DC++_5") (pintype "bidirectional"))
    )
    (net (code "101") (name "Net-(ETH_IN5-6-RECEIVE-)") (class "Default")
      (node (ref "ETH_IN5") (pin "6") (pinfunction "6-RECEIVE-_6") (pintype "bidirectional"))
      (node (ref "ETH_OUT5") (pin "6") (pinfunction "6-RECEIVE-_6") (pintype "bidirectional"))
    )
    (net (code "102") (name "Net-(ETH_IN5-7-DC--)") (class "Default")
      (node (ref "ETH_IN5") (pin "7") (pinfunction "7-DC--_7") (pintype "bidirectional"))
      (node (ref "ETH_OUT5") (pin "7") (pinfunction "7-DC--_7") (pintype "bidirectional"))
    )
    (net (code "103") (name "Net-(ETH_IN5-8-DC-)") (class "Default")
      (node (ref "ETH_IN5") (pin "8") (pinfunction "8-DC-_8") (pintype "bidirectional"))
      (node (ref "ETH_OUT5") (pin "8") (pinfunction "8-DC-_8") (pintype "bidirectional"))
    )
    (net (code "104") (name "Net-(ETH_IN6-1-TRANS+)") (class "Default")
      (node (ref "ETH_IN6") (pin "1") (pinfunction "1-TRANS+_1") (pintype "bidirectional"))
      (node (ref "ETH_OUT6") (pin "1") (pinfunction "1-TRANS+_1") (pintype "bidirectional"))
    )
    (net (code "105") (name "Net-(ETH_IN6-2-TRANS-)") (class "Default")
      (node (ref "ETH_IN6") (pin "2") (pinfunction "2-TRANS-_2") (pintype "bidirectional"))
      (node (ref "ETH_OUT6") (pin "2") (pinfunction "2-TRANS-_2") (pintype "bidirectional"))
    )
    (net (code "106") (name "Net-(ETH_IN6-3+RECEIVE+)") (class "Default")
      (node (ref "ETH_IN6") (pin "3") (pinfunction "3+RECEIVE+_3") (pintype "bidirectional"))
      (node (ref "ETH_OUT6") (pin "3") (pinfunction "3+RECEIVE+_3") (pintype "bidirectional"))
    )
    (net (code "107") (name "Net-(ETH_IN6-4-DC+)") (class "Default")
      (node (ref "ETH_IN6") (pin "4") (pinfunction "4-DC+_4") (pintype "bidirectional"))
      (node (ref "ETH_OUT6") (pin "4") (pinfunction "4-DC+_4") (pintype "bidirectional"))
    )
    (net (code "108") (name "Net-(ETH_IN6-5-DC++)") (class "Default")
      (node (ref "ETH_IN6") (pin "5") (pinfunction "5-DC++_5") (pintype "bidirectional"))
      (node (ref "ETH_OUT6") (pin "5") (pinfunction "5-DC++_5") (pintype "bidirectional"))
    )
    (net (code "109") (name "Net-(ETH_IN6-6-RECEIVE-)") (class "Default")
      (node (ref "ETH_IN6") (pin "6") (pinfunction "6-RECEIVE-_6") (pintype "bidirectional"))
      (node (ref "ETH_OUT6") (pin "6") (pinfunction "6-RECEIVE-_6") (pintype "bidirectional"))
    )
    (net (code "110") (name "Net-(ETH_IN6-7-DC--)") (class "Default")
      (node (ref "ETH_IN6") (pin "7") (pinfunction "7-DC--_7") (pintype "bidirectional"))
      (node (ref "ETH_OUT6") (pin "7") (pinfunction "7-DC--_7") (pintype "bidirectional"))
    )
    (net (code "111") (name "Net-(ETH_IN6-8-DC-)") (class "Default")
      (node (ref "ETH_IN6") (pin "8") (pinfunction "8-DC-_8") (pintype "bidirectional"))
      (node (ref "ETH_OUT6") (pin "8") (pinfunction "8-DC-_8") (pintype "bidirectional"))
    )
    (net (code "112") (name "unconnected-(JP1-Pad1)") (class "Default")
      (node (ref "JP1") (pin "1") (pinfunction "1_1") (pintype "passive"))
    )
    (net (code "113") (name "unconnected-(JP1-Pad2)") (class "Default")
      (node (ref "JP1") (pin "2") (pinfunction "2_2") (pintype "passive"))
    )
    (net (code "114") (name "unconnected-(JP1-Pad3)") (class "Default")
      (node (ref "JP1") (pin "3") (pinfunction "3_3") (pintype "passive"))
    )
    (net (code "115") (name "unconnected-(JP1-Pad4)") (class "Default")
      (node (ref "JP1") (pin "4") (pinfunction "4_4") (pintype "passive"))
    )
    (net (code "116") (name "unconnected-(JP1-Pad5)") (class "Default")
      (node (ref "JP1") (pin "5") (pinfunction "5_5") (pintype "passive"))
    )
    (net (code "117") (name "unconnected-(JP1-Pad6)") (class "Default")
      (node (ref "JP1") (pin "6") (pinfunction "6_6") (pintype "passive"))
    )
    (net (code "118") (name "unconnected-(JP1-Pad7)") (class "Default")
      (node (ref "JP1") (pin "7") (pinfunction "7_7") (pintype "passive"))
    )
    (net (code "119") (name "unconnected-(JP1-Pad8)") (class "Default")
      (node (ref "JP1") (pin "8") (pinfunction "8_8") (pintype "passive"))
    )
    (net (code "120") (name "unconnected-(JP1-Pad9)") (class "Default")
      (node (ref "JP1") (pin "9") (pinfunction "9_9") (pintype "passive"))
    )
    (net (code "121") (name "unconnected-(JP1-Pad10)") (class "Default")
      (node (ref "JP1") (pin "10") (pinfunction "10_10") (pintype "passive"))
    )
    (net (code "122") (name "unconnected-(JP1-Pad11)") (class "Default")
      (node (ref "JP1") (pin "11") (pinfunction "11_11") (pintype "passive"))
    )
    (net (code "123") (name "unconnected-(JP1-Pad12)") (class "Default")
      (node (ref "JP1") (pin "12") (pinfunction "12_12") (pintype "passive"))
    )
    (net (code "124") (name "unconnected-(JP1-Pad13)") (class "Default")
      (node (ref "JP1") (pin "13") (pinfunction "13_13") (pintype "passive"))
    )
    (net (code "125") (name "unconnected-(JP1-Pad14)") (class "Default")
      (node (ref "JP1") (pin "14") (pinfunction "14_14") (pintype "passive"))
    )
    (net (code "126") (name "unconnected-(JP1-Pad15)") (class "Default")
      (node (ref "JP1") (pin "15") (pinfunction "15_15") (pintype "passive"))
    )
    (net (code "127") (name "unconnected-(JP1-Pad16)") (class "Default")
      (node (ref "JP1") (pin "16") (pinfunction "16_16") (pintype "passive"))
    )
    (net (code "128") (name "unconnected-(RS-485_OUT1-4-DC+-Pad4)") (class "Default")
      (node (ref "RS-485_OUT1") (pin "4") (pinfunction "4-DC+_4") (pintype "bidirectional"))
    )
    (net (code "129") (name "unconnected-(RS-485_OUT1-5-DC++-Pad5)") (class "Default")
      (node (ref "RS-485_OUT1") (pin "5") (pinfunction "5-DC++_5") (pintype "bidirectional"))
    )
    (net (code "130") (name "unconnected-(RS-485_OUT1-7-DC---Pad7)") (class "Default")
      (node (ref "RS-485_OUT1") (pin "7") (pinfunction "7-DC--_7") (pintype "bidirectional"))
    )
    (net (code "131") (name "unconnected-(RS-485_OUT1-8-DC--Pad8)") (class "Default")
      (node (ref "RS-485_OUT1") (pin "8") (pinfunction "8-DC-_8") (pintype "bidirectional"))
    )
    (net (code "132") (name "unconnected-(RS-485_OUT2-4-DC+-Pad4)") (class "Default")
      (node (ref "RS-485_OUT2") (pin "4") (pinfunction "4-DC+_4") (pintype "bidirectional"))
    )
    (net (code "133") (name "unconnected-(RS-485_OUT2-5-DC++-Pad5)") (class "Default")
      (node (ref "RS-485_OUT2") (pin "5") (pinfunction "5-DC++_5") (pintype "bidirectional"))
    )
    (net (code "134") (name "unconnected-(RS-485_OUT2-7-DC---Pad7)") (class "Default")
      (node (ref "RS-485_OUT2") (pin "7") (pinfunction "7-DC--_7") (pintype "bidirectional"))
    )
    (net (code "135") (name "unconnected-(RS-485_OUT2-8-DC--Pad8)") (class "Default")
      (node (ref "RS-485_OUT2") (pin "8") (pinfunction "8-DC-_8") (pintype "bidirectional"))
    )
    (net (code "136") (name "unconnected-(RS-485_OUT3-4-DC+-Pad4)") (class "Default")
      (node (ref "RS-485_OUT3") (pin "4") (pinfunction "4-DC+_4") (pintype "bidirectional"))
    )
    (net (code "137") (name "unconnected-(RS-485_OUT3-5-DC++-Pad5)") (class "Default")
      (node (ref "RS-485_OUT3") (pin "5") (pinfunction "5-DC++_5") (pintype "bidirectional"))
    )
    (net (code "138") (name "unconnected-(RS-485_OUT3-7-DC---Pad7)") (class "Default")
      (node (ref "RS-485_OUT3") (pin "7") (pinfunction "7-DC--_7") (pintype "bidirectional"))
    )
    (net (code "139") (name "unconnected-(RS-485_OUT3-8-DC--Pad8)") (class "Default")
      (node (ref "RS-485_OUT3") (pin "8") (pinfunction "8-DC-_8") (pintype "bidirectional"))
    )
    (net (code "140") (name "unconnected-(RS-485_OUT4-4-DC+-Pad4)") (class "Default")
      (node (ref "RS-485_OUT4") (pin "4") (pinfunction "4-DC+_4") (pintype "bidirectional"))
    )
    (net (code "141") (name "unconnected-(RS-485_OUT4-5-DC++-Pad5)") (class "Default")
      (node (ref "RS-485_OUT4") (pin "5") (pinfunction "5-DC++_5") (pintype "bidirectional"))
    )
    (net (code "142") (name "unconnected-(RS-485_OUT4-7-DC---Pad7)") (class "Default")
      (node (ref "RS-485_OUT4") (pin "7") (pinfunction "7-DC--_7") (pintype "bidirectional"))
    )
    (net (code "143") (name "unconnected-(RS-485_OUT4-8-DC--Pad8)") (class "Default")
      (node (ref "RS-485_OUT4") (pin "8") (pinfunction "8-DC-_8") (pintype "bidirectional"))
    )
    (net (code "144") (name "unconnected-(RS-485_OUT5-4-DC+-Pad4)") (class "Default")
      (node (ref "RS-485_OUT5") (pin "4") (pinfunction "4-DC+_4") (pintype "bidirectional"))
    )
    (net (code "145") (name "unconnected-(RS-485_OUT5-6-RECEIVE--Pad6)") (class "Default")
      (node (ref "RS-485_OUT5") (pin "6") (pinfunction "6-RECEIVE-_6") (pintype "bidirectional"))
    )
    (net (code "146") (name "unconnected-(RS-485_OUT5-7-DC---Pad7)") (class "Default")
      (node (ref "RS-485_OUT5") (pin "7") (pinfunction "7-DC--_7") (pintype "bidirectional"))
    )
    (net (code "147") (name "unconnected-(RS-485_OUT5-8-DC--Pad8)") (class "Default")
      (node (ref "RS-485_OUT5") (pin "8") (pinfunction "8-DC-_8") (pintype "bidirectional"))
    )
    (net (code "148") (name "unconnected-(RS-485_OUT6-4-DC+-Pad4)") (class "Default")
      (node (ref "RS-485_OUT6") (pin "4") (pinfunction "4-DC+_4") (pintype "bidirectional"))
    )
    (net (code "149") (name "unconnected-(RS-485_OUT6-5-DC++-Pad5)") (class "Default")
      (node (ref "RS-485_OUT6") (pin "5") (pinfunction "5-DC++_5") (pintype "bidirectional"))
    )
    (net (code "150") (name "unconnected-(RS-485_OUT6-7-DC---Pad7)") (class "Default")
      (node (ref "RS-485_OUT6") (pin "7") (pinfunction "7-DC--_7") (pintype "bidirectional"))
    )
    (net (code "151") (name "unconnected-(RS-485_OUT6-8-DC--Pad8)") (class "Default")
      (node (ref "RS-485_OUT6") (pin "8") (pinfunction "8-DC-_8") (pintype "bidirectional"))
    )
    (net (code "152") (name "unconnected-(RS-485_OUT7-4-DC+-Pad4)") (class "Default")
      (node (ref "RS-485_OUT7") (pin "4") (pinfunction "4-DC+_4") (pintype "bidirectional"))
    )
    (net (code "153") (name "unconnected-(RS-485_OUT7-5-DC++-Pad5)") (class "Default")
      (node (ref "RS-485_OUT7") (pin "5") (pinfunction "5-DC++_5") (pintype "bidirectional"))
    )
    (net (code "154") (name "unconnected-(RS-485_OUT7-7-DC---Pad7)") (class "Default")
      (node (ref "RS-485_OUT7") (pin "7") (pinfunction "7-DC--_7") (pintype "bidirectional"))
    )
    (net (code "155") (name "unconnected-(RS-485_OUT7-8-DC--Pad8)") (class "Default")
      (node (ref "RS-485_OUT7") (pin "8") (pinfunction "8-DC-_8") (pintype "bidirectional"))
    )
    (net (code "156") (name "unconnected-(RS-485_OUT8-4-DC+-Pad4)") (class "Default")
      (node (ref "RS-485_OUT8") (pin "4") (pinfunction "4-DC+_4") (pintype "bidirectional"))
    )
    (net (code "157") (name "unconnected-(RS-485_OUT8-5-DC++-Pad5)") (class "Default")
      (node (ref "RS-485_OUT8") (pin "5") (pinfunction "5-DC++_5") (pintype "bidirectional"))
    )
    (net (code "158") (name "unconnected-(RS-485_OUT8-7-DC---Pad7)") (class "Default")
      (node (ref "RS-485_OUT8") (pin "7") (pinfunction "7-DC--_7") (pintype "bidirectional"))
    )
    (net (code "159") (name "unconnected-(RS-485_OUT8-8-DC--Pad8)") (class "Default")
      (node (ref "RS-485_OUT8") (pin "8") (pinfunction "8-DC-_8") (pintype "bidirectional"))
    )
    (net (code "160") (name "unconnected-(RS-485_OUT9-4-DC+-Pad4)") (class "Default")
      (node (ref "RS-485_OUT9") (pin "4") (pinfunction "4-DC+_4") (pintype "bidirectional"))
    )
    (net (code "161") (name "unconnected-(RS-485_OUT9-5-DC++-Pad5)") (class "Default")
      (node (ref "RS-485_OUT9") (pin "5") (pinfunction "5-DC++_5") (pintype "bidirectional"))
    )
    (net (code "162") (name "unconnected-(RS-485_OUT9-7-DC---Pad7)") (class "Default")
      (node (ref "RS-485_OUT9") (pin "7") (pinfunction "7-DC--_7") (pintype "bidirectional"))
    )
    (net (code "163") (name "unconnected-(RS-485_OUT9-8-DC--Pad8)") (class "Default")
      (node (ref "RS-485_OUT9") (pin "8") (pinfunction "8-DC-_8") (pintype "bidirectional"))
    )
    (net (code "164") (name "unconnected-(RS-485_OUT10-4-DC+-Pad4)") (class "Default")
      (node (ref "RS-485_OUT10") (pin "4") (pinfunction "4-DC+_4") (pintype "bidirectional"))
    )
    (net (code "165") (name "unconnected-(RS-485_OUT10-5-DC++-Pad5)") (class "Default")
      (node (ref "RS-485_OUT10") (pin "5") (pinfunction "5-DC++_5") (pintype "bidirectional"))
    )
    (net (code "166") (name "unconnected-(RS-485_OUT10-7-DC---Pad7)") (class "Default")
      (node (ref "RS-485_OUT10") (pin "7") (pinfunction "7-DC--_7") (pintype "bidirectional"))
    )
    (net (code "167") (name "unconnected-(RS-485_OUT10-8-DC--Pad8)") (class "Default")
      (node (ref "RS-485_OUT10") (pin "8") (pinfunction "8-DC-_8") (pintype "bidirectional"))
    )
    (net (code "168") (name "unconnected-(RS-485_OUT11-4-DC+-Pad4)") (class "Default")
      (node (ref "RS-485_OUT11") (pin "4") (pinfunction "4-DC+_4") (pintype "bidirectional"))
    )
    (net (code "169") (name "unconnected-(RS-485_OUT11-5-DC++-Pad5)") (class "Default")
      (node (ref "RS-485_OUT11") (pin "5") (pinfunction "5-DC++_5") (pintype "bidirectional"))
    )
    (net (code "170") (name "unconnected-(RS-485_OUT11-7-DC---Pad7)") (class "Default")
      (node (ref "RS-485_OUT11") (pin "7") (pinfunction "7-DC--_7") (pintype "bidirectional"))
    )
    (net (code "171") (name "unconnected-(RS-485_OUT11-8-DC--Pad8)") (class "Default")
      (node (ref "RS-485_OUT11") (pin "8") (pinfunction "8-DC-_8") (pintype "bidirectional"))
    )
    (net (code "172") (name "unconnected-(RS-485_OUT12-4-DC+-Pad4)") (class "Default")
      (node (ref "RS-485_OUT12") (pin "4") (pinfunction "4-DC+_4") (pintype "bidirectional"))
    )
    (net (code "173") (name "unconnected-(RS-485_OUT12-5-DC++-Pad5)") (class "Default")
      (node (ref "RS-485_OUT12") (pin "5") (pinfunction "5-DC++_5") (pintype "bidirectional"))
    )
    (net (code "174") (name "unconnected-(RS-485_OUT12-7-DC---Pad7)") (class "Default")
      (node (ref "RS-485_OUT12") (pin "7") (pinfunction "7-DC--_7") (pintype "bidirectional"))
    )
    (net (code "175") (name "unconnected-(RS-485_OUT12-8-DC--Pad8)") (class "Default")
      (node (ref "RS-485_OUT12") (pin "8") (pinfunction "8-DC-_8") (pintype "bidirectional"))
    )
    (net (code "176") (name "unconnected-(U$1-Pad49)") (class "Default")
      (node (ref "U$1") (pin "49") (pinfunction "49_49") (pintype "bidirectional"))
    )
    (net (code "177") (name "unconnected-(U$1-Pad50)") (class "Default")
      (node (ref "U$1") (pin "50") (pinfunction "50_50") (pintype "bidirectional"))
    )
    (net (code "178") (name "unconnected-(U$1-Pad51)") (class "Default")
      (node (ref "U$1") (pin "51") (pinfunction "51_51") (pintype "bidirectional"))
    )
    (net (code "179") (name "unconnected-(U$1-Pad52)") (class "Default")
      (node (ref "U$1") (pin "52") (pinfunction "52_52") (pintype "bidirectional"))
    )
    (net (code "180") (name "unconnected-(U$1-Pad53)") (class "Default")
      (node (ref "U$1") (pin "53") (pinfunction "53_53") (pintype "bidirectional"))
    )
    (net (code "181") (name "unconnected-(U$1-Pad54)") (class "Default")
      (node (ref "U$1") (pin "54") (pinfunction "54_54") (pintype "bidirectional"))
    )
    (net (code "182") (name "unconnected-(U$1-Pad55)") (class "Default")
      (node (ref "U$1") (pin "55") (pinfunction "55_55") (pintype "bidirectional"))
    )
    (net (code "183") (name "unconnected-(U$1-Pad56)") (class "Default")
      (node (ref "U$1") (pin "56") (pinfunction "56_56") (pintype "bidirectional"))
    )
    (net (code "184") (name "unconnected-(U$1-Pad57)") (class "Default")
      (node (ref "U$1") (pin "57") (pinfunction "57_57") (pintype "bidirectional"))
    )
    (net (code "185") (name "unconnected-(U$1-Pad58)") (class "Default")
      (node (ref "U$1") (pin "58") (pinfunction "58_58") (pintype "bidirectional"))
    )
    (net (code "186") (name "unconnected-(U$1-Pad59)") (class "Default")
      (node (ref "U$1") (pin "59") (pinfunction "59_59") (pintype "bidirectional"))
    )
    (net (code "187") (name "unconnected-(U$1-Pad60)") (class "Default")
      (node (ref "U$1") (pin "60") (pinfunction "60_60") (pintype "bidirectional"))
    )
    (net (code "188") (name "unconnected-(U$1-Pad61)") (class "Default")
      (node (ref "U$1") (pin "61") (pinfunction "61_61") (pintype "bidirectional"))
    )
    (net (code "189") (name "unconnected-(U$1-Pad62)") (class "Default")
      (node (ref "U$1") (pin "62") (pinfunction "62_62") (pintype "bidirectional"))
    )
    (net (code "190") (name "unconnected-(U$1-Pad63)") (class "Default")
      (node (ref "U$1") (pin "63") (pinfunction "63_63") (pintype "bidirectional"))
    )
    (net (code "191") (name "unconnected-(U$1-Pad64)") (class "Default")
      (node (ref "U$1") (pin "64") (pinfunction "64_64") (pintype "bidirectional"))
    )
    (net (code "192") (name "unconnected-(U$1-Pad65)") (class "Default")
      (node (ref "U$1") (pin "65") (pinfunction "65_65") (pintype "bidirectional"))
    )
    (net (code "193") (name "unconnected-(U$1-Pad66)") (class "Default")
      (node (ref "U$1") (pin "66") (pinfunction "66_66") (pintype "bidirectional"))
    )
    (net (code "194") (name "unconnected-(U$1-Pad67)") (class "Default")
      (node (ref "U$1") (pin "67") (pinfunction "67_67") (pintype "bidirectional"))
    )
    (net (code "195") (name "unconnected-(U$1-Pad68)") (class "Default")
      (node (ref "U$1") (pin "68") (pinfunction "68_68") (pintype "bidirectional"))
    )
  )
)
